# ESP_power.net
KiCad netlist of a schematic drawn in Altium Designer
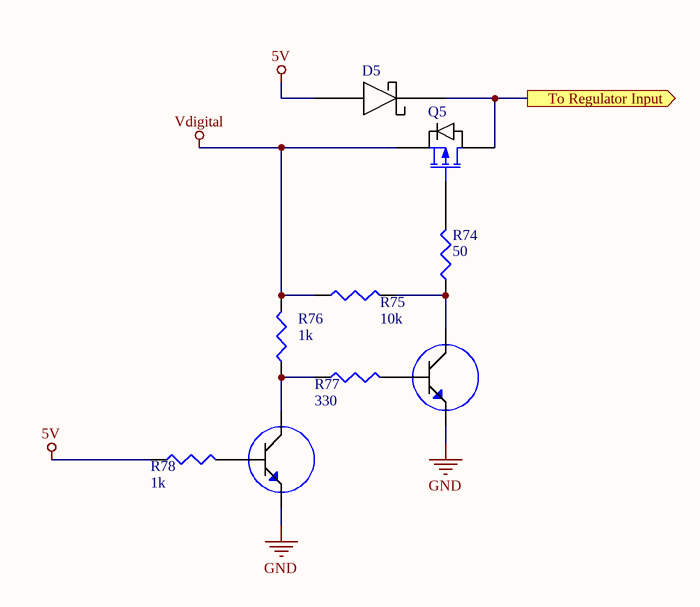
[diagram p0: ESP power.SchDoc]

(export (version "E")
  (design (tool "Eeschema 10.0.6"))
  (components
    (comp (ref "D5")
      (value "Buck Diode")
      (footprint "*DO-214AC")
      (libsource (lib "AvionicsParts") (part "Buck Diode"))
    )
    (comp (ref "Q5")
      (value "P-Channel")
      (footprint "P Channel MOSFET")
      (libsource (lib "AvionicsParts") (part "P-Channel"))
    )
    (comp (ref "R74")
      (value "50")
      (footprint "0603 to 0805 SMD")
      (description "Resistor")
      (fields (field (name "Comment") "Res3") (field (name "PUBLISHER") "Altium Limited"))
      (libsource (lib "Miscellaneous Devices") (part "Res3"))
    )
    (comp (ref "R75")
      (value "10k")
      (footprint "0603 to 0805 SMD")
      (description "Resistor")
      (fields (field (name "Comment") "Res3") (field (name "PUBLISHER") "Altium Limited"))
      (libsource (lib "Miscellaneous Devices") (part "Res3"))
    )
    (comp (ref "R76")
      (value "1k")
      (footprint "0603 to 0805 SMD")
      (description "Resistor")
      (fields (field (name "Comment") "Res3") (field (name "PUBLISHER") "Altium Limited"))
      (libsource (lib "Miscellaneous Devices") (part "Res3"))
    )
    (comp (ref "R77")
      (value "330")
      (footprint "0603 to 0805 SMD")
      (description "Resistor")
      (fields (field (name "Comment") "Res3") (field (name "PUBLISHER") "Altium Limited"))
      (libsource (lib "Miscellaneous Devices") (part "Res3"))
    )
    (comp (ref "R78")
      (value "1k")
      (footprint "0603 to 0805 SMD")
      (description "Resistor")
      (fields (field (name "Comment") "Res3") (field (name "PUBLISHER") "Altium Limited"))
      (libsource (lib "Miscellaneous Devices") (part "Res3"))
    )
    (comp (ref "T10")
      (value "MMBT2222ALT1")
      (footprint "BJT")
      (description "Trans NPN 40V 0.6A SOT23")
      (fields (field (name "MF") "ON Semiconductor"))
      (libsource (lib "AvionicsParts") (part "BJT NPN"))
    )
    (comp (ref "T11")
      (value "MMBT2222ALT1")
      (footprint "BJT")
      (description "Trans NPN 40V 0.6A SOT23")
      (fields (field (name "MF") "ON Semiconductor"))
      (libsource (lib "AvionicsParts") (part "BJT NPN"))
    )
  )
  (nets
    (net (code "1") (name "/To Regulator Input") (class "Default")
      (node (ref "D5") (pin "2") (pinfunction "C_2") (pintype "passive"))
      (node (ref "Q5") (pin "3") (pinfunction "D_3") (pintype "passive"))
    )
    (net (code "2") (name "5V") (class "Default")
      (node (ref "D5") (pin "1") (pinfunction "A_1") (pintype "passive"))
      (node (ref "R78") (pin "1") (pinfunction "1_1") (pintype "passive"))
    )
    (net (code "3") (name "GND") (class "Default")
      (node (ref "T10") (pin "2") (pinfunction "E_2") (pintype "passive"))
      (node (ref "T11") (pin "2") (pinfunction "E_2") (pintype "passive"))
    )
    (net (code "4") (name "Net-(Q5-G)") (class "Default")
      (node (ref "Q5") (pin "1") (pinfunction "G_1") (pintype "passive"))
      (node (ref "R74") (pin "2") (pinfunction "2_2") (pintype "passive"))
    )
    (net (code "5") (name "Net-(T10-B)") (class "Default")
      (node (ref "R77") (pin "2") (pinfunction "2_2") (pintype "passive"))
      (node (ref "T10") (pin "1") (pinfunction "B_1") (pintype "passive"))
    )
    (net (code "6") (name "Net-(T10-C)") (class "Default")
      (node (ref "R74") (pin "1") (pinfunction "1_1") (pintype "passive"))
      (node (ref "R75") (pin "2") (pinfunction "2_2") (pintype "passive"))
      (node (ref "T10") (pin "3") (pinfunction "C_3") (pintype "passive"))
    )
    (net (code "7") (name "Net-(T11-B)") (class "Default")
      (node (ref "R78") (pin "2") (pinfunction "2_2") (pintype "passive"))
      (node (ref "T11") (pin "1") (pinfunction "B_1") (pintype "passive"))
    )
    (net (code "8") (name "Net-(T11-C)") (class "Default")
      (node (ref "R76") (pin "1") (pinfunction "1_1") (pintype "passive"))
      (node (ref "R77") (pin "1") (pinfunction "1_1") (pintype "passive"))
      (node (ref "T11") (pin "3") (pinfunction "C_3") (pintype "passive"))
    )
    (net (code "9") (name "Vdigital") (class "Default")
      (node (ref "Q5") (pin "2") (pinfunction "S_2") (pintype "passive"))
      (node (ref "R75") (pin "1") (pinfunction "1_1") (pintype "passive"))
      (node (ref "R76") (pin "2") (pinfunction "2_2") (pintype "passive"))
    )
  )
)
